# MCB-iMX7-WARP-v1_0_0.net
KiCad netlist of a schematic drawn in EAGLE
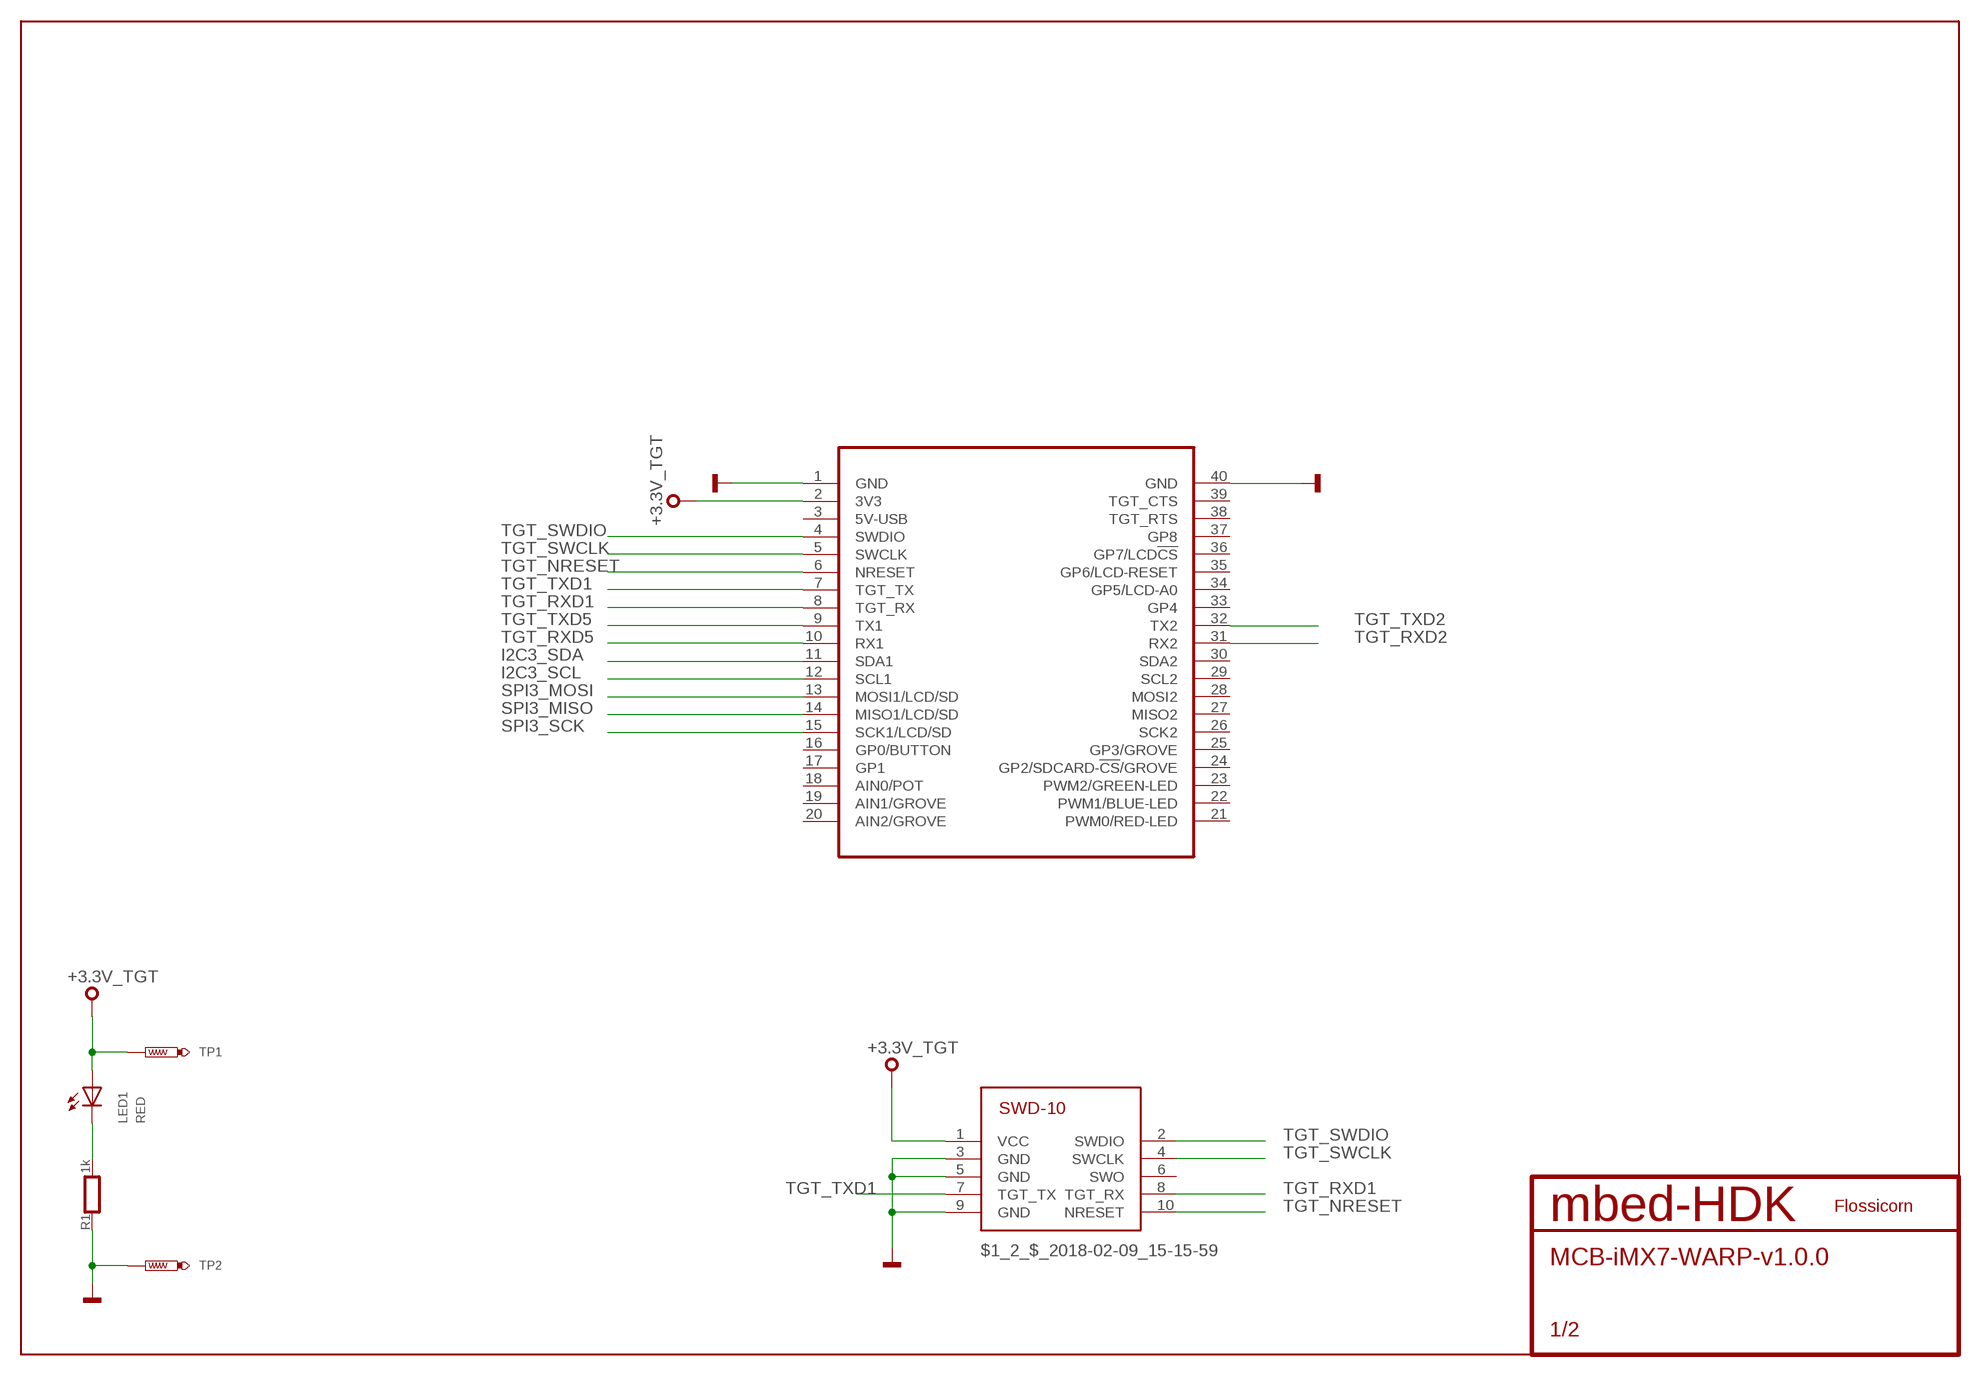
[diagram p0: schematic, sheet 1]
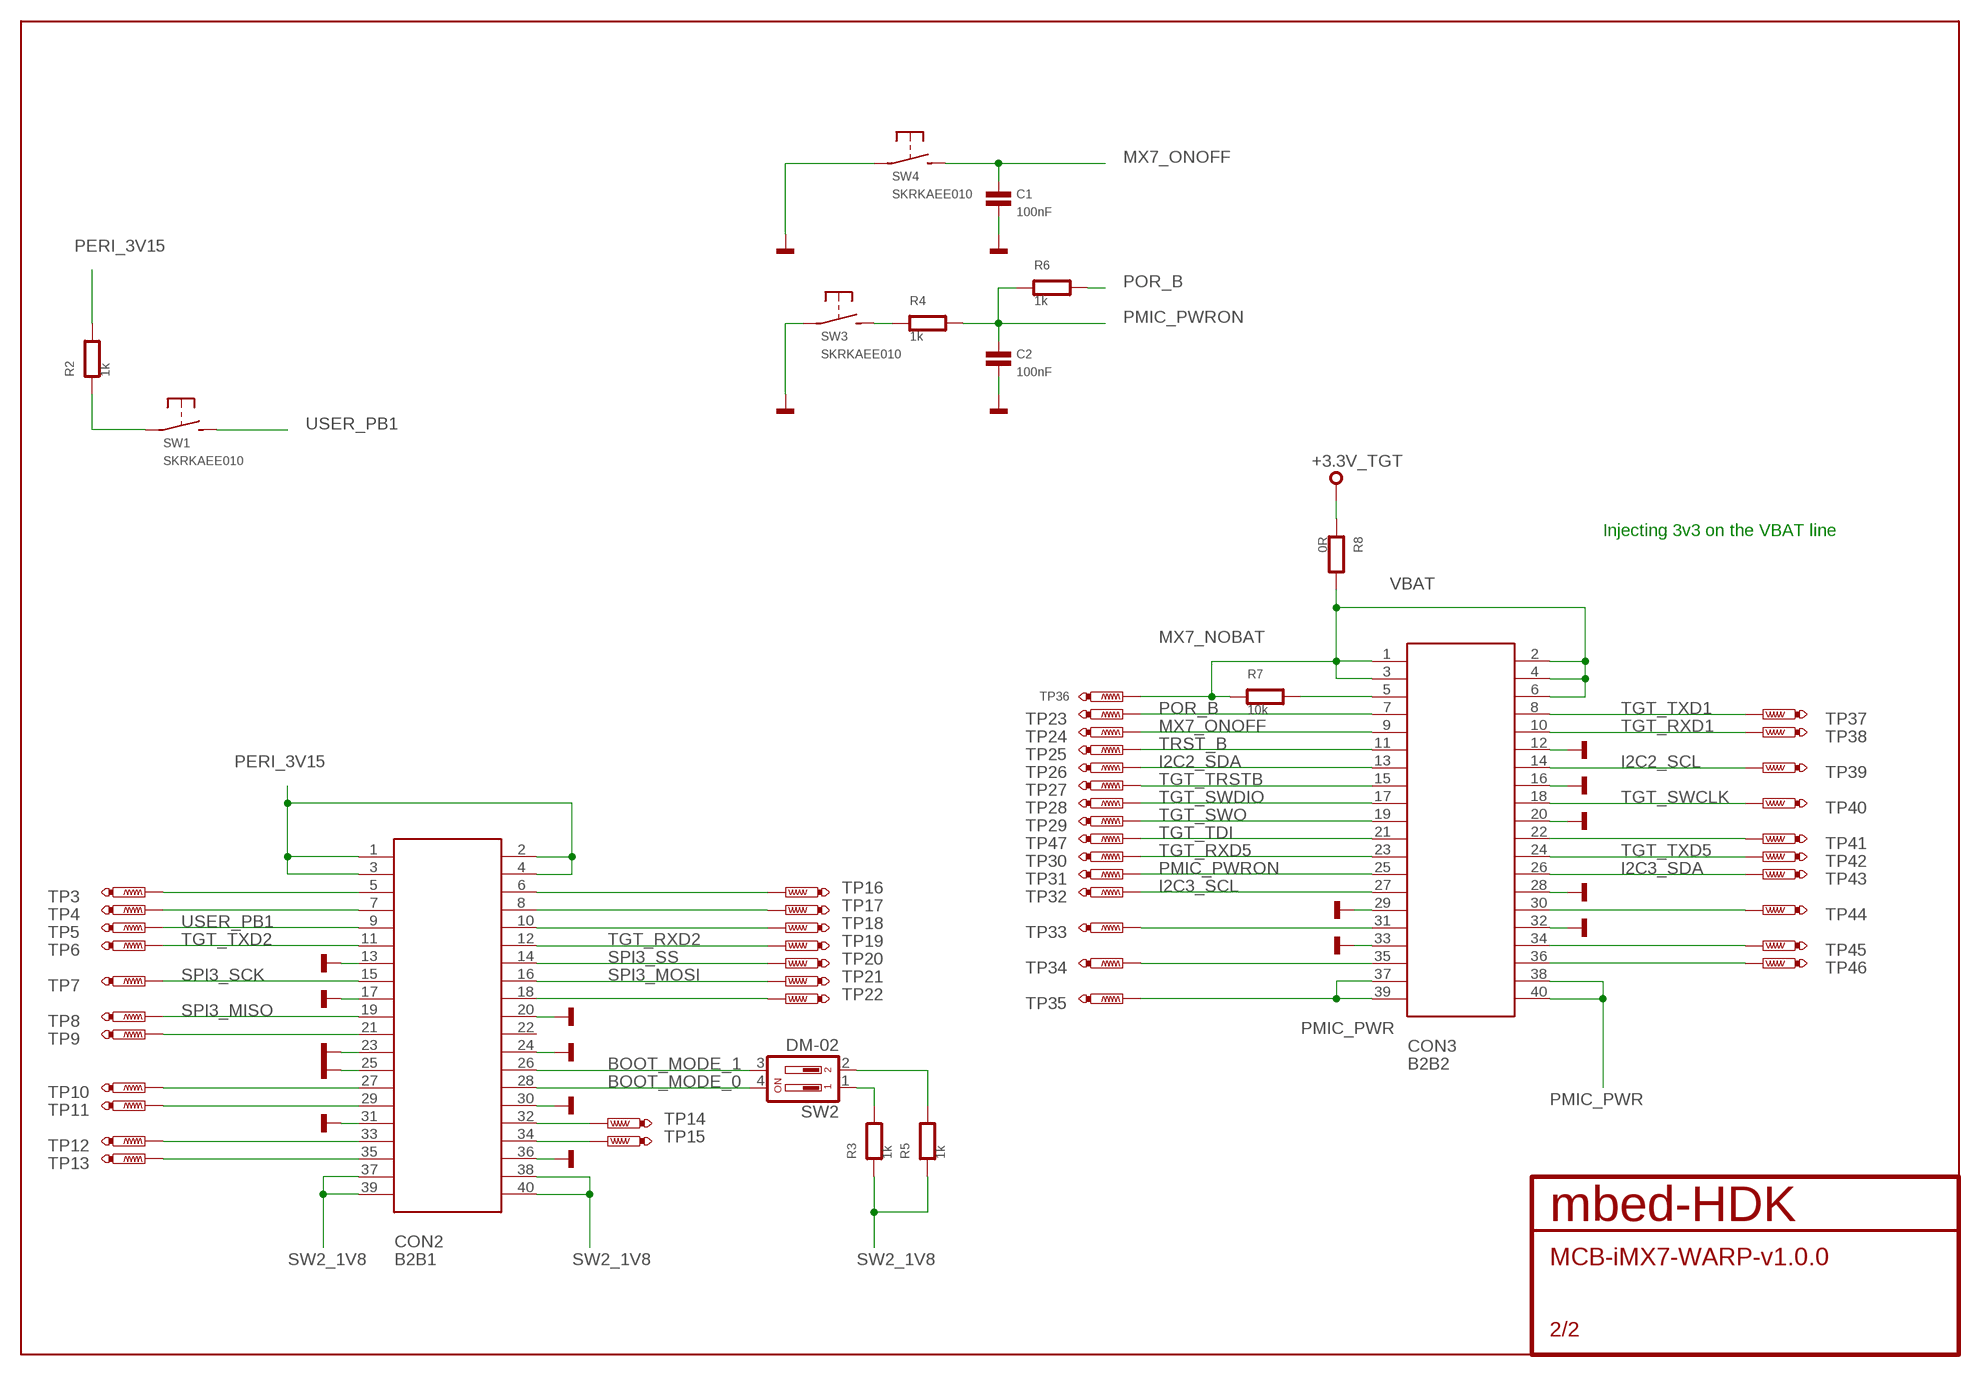
[diagram p1: schematic, sheet 2]

(export (version "E")
  (design (tool "Eeschema 10.0.6"))
  (components
    (comp (ref "C1")
      (value "100nF")
      (footprint "eagle-import:0603")
      (libsource (lib "eagle-import") (part "CAPACITOR0603"))
    )
    (comp (ref "C2")
      (value "100nF")
      (footprint "eagle-import:0603")
      (libsource (lib "eagle-import") (part "CAPACITOR0603"))
    )
    (comp (ref "CON2")
      (value "B2B1")
      (footprint "eagle-import:DF40HC-XX-40DS-XX-V")
      (libsource (lib "eagle-import") (part "DF40HC-XX-40DS-XX-V"))
    )
    (comp (ref "CON3")
      (value "B2B2")
      (footprint "eagle-import:DF40HC-XX-40DS-XX-V")
      (libsource (lib "eagle-import") (part "DF40HC-XX-40DS-XX-V"))
    )
    (comp (ref "R2")
      (value "1k")
      (footprint "eagle-import:0603")
      (libsource (lib "eagle-import") (part "RESISTOR0603"))
    )
    (comp (ref "R3")
      (value "1k")
      (footprint "eagle-import:0603")
      (libsource (lib "eagle-import") (part "RESISTOR0603"))
    )
    (comp (ref "R4")
      (value "1k")
      (footprint "eagle-import:0603")
      (libsource (lib "eagle-import") (part "RESISTOR0603"))
    )
    (comp (ref "R5")
      (value "1k")
      (footprint "eagle-import:0603")
      (libsource (lib "eagle-import") (part "RESISTOR0603"))
    )
    (comp (ref "R6")
      (value "1k")
      (footprint "eagle-import:0603")
      (libsource (lib "eagle-import") (part "RESISTOR0603"))
    )
    (comp (ref "R7")
      (value "10k")
      (footprint "eagle-import:0603")
      (libsource (lib "eagle-import") (part "RESISTOR0603"))
    )
    (comp (ref "R8")
      (value "0R")
      (footprint "eagle-import:0603")
      (libsource (lib "eagle-import") (part "RESISTOR0603"))
    )
    (comp (ref "SW1")
      (value "SKRKAEE010")
      (footprint "eagle-import:SKRKAEE010")
      (fields (field (name "MF") "ALPS"))
      (libsource (lib "eagle-import") (part "SKRKAEE010"))
    )
    (comp (ref "SW2")
      (value "DM-02")
      (footprint "eagle-import:DM-02")
      (libsource (lib "eagle-import") (part "DM-02"))
    )
    (comp (ref "SW3")
      (value "SKRKAEE010")
      (footprint "eagle-import:SKRKAEE010")
      (fields (field (name "MF") "ALPS"))
      (libsource (lib "eagle-import") (part "SKRKAEE010"))
    )
    (comp (ref "SW4")
      (value "SKRKAEE010")
      (footprint "eagle-import:SKRKAEE010")
      (fields (field (name "MF") "ALPS"))
      (libsource (lib "eagle-import") (part "SKRKAEE010"))
    )
    (comp (ref "TP3")
      (value "PTR1TP06R")
      (footprint "eagle-import:TP06R")
      (libsource (lib "eagle-import") (part "PTR1TP06R"))
    )
    (comp (ref "TP4")
      (value "PTR1TP06R")
      (footprint "eagle-import:TP06R")
      (libsource (lib "eagle-import") (part "PTR1TP06R"))
    )
    (comp (ref "TP5")
      (value "PTR1TP06R")
      (footprint "eagle-import:TP06R")
      (libsource (lib "eagle-import") (part "PTR1TP06R"))
    )
    (comp (ref "TP6")
      (value "PTR1TP06R")
      (footprint "eagle-import:TP06R")
      (libsource (lib "eagle-import") (part "PTR1TP06R"))
    )
    (comp (ref "TP7")
      (value "PTR1TP06R")
      (footprint "eagle-import:TP06R")
      (libsource (lib "eagle-import") (part "PTR1TP06R"))
    )
    (comp (ref "TP8")
      (value "PTR1TP06R")
      (footprint "eagle-import:TP06R")
      (libsource (lib "eagle-import") (part "PTR1TP06R"))
    )
    (comp (ref "TP9")
      (value "PTR1TP06R")
      (footprint "eagle-import:TP06R")
      (libsource (lib "eagle-import") (part "PTR1TP06R"))
    )
    (comp (ref "TP10")
      (value "PTR1TP06R")
      (footprint "eagle-import:TP06R")
      (libsource (lib "eagle-import") (part "PTR1TP06R"))
    )
    (comp (ref "TP11")
      (value "PTR1TP06R")
      (footprint "eagle-import:TP06R")
      (libsource (lib "eagle-import") (part "PTR1TP06R"))
    )
    (comp (ref "TP12")
      (value "PTR1TP06R")
      (footprint "eagle-import:TP06R")
      (libsource (lib "eagle-import") (part "PTR1TP06R"))
    )
    (comp (ref "TP13")
      (value "PTR1TP06R")
      (footprint "eagle-import:TP06R")
      (libsource (lib "eagle-import") (part "PTR1TP06R"))
    )
    (comp (ref "TP14")
      (value "PTR1TP06R")
      (footprint "eagle-import:TP06R")
      (libsource (lib "eagle-import") (part "PTR1TP06R"))
    )
    (comp (ref "TP15")
      (value "PTR1TP06R")
      (footprint "eagle-import:TP06R")
      (libsource (lib "eagle-import") (part "PTR1TP06R"))
    )
    (comp (ref "TP16")
      (value "PTR1TP06R")
      (footprint "eagle-import:TP06R")
      (libsource (lib "eagle-import") (part "PTR1TP06R"))
    )
    (comp (ref "TP17")
      (value "PTR1TP06R")
      (footprint "eagle-import:TP06R")
      (libsource (lib "eagle-import") (part "PTR1TP06R"))
    )
    (comp (ref "TP18")
      (value "PTR1TP06R")
      (footprint "eagle-import:TP06R")
      (libsource (lib "eagle-import") (part "PTR1TP06R"))
    )
    (comp (ref "TP19")
      (value "PTR1TP06R")
      (footprint "eagle-import:TP06R")
      (libsource (lib "eagle-import") (part "PTR1TP06R"))
    )
    (comp (ref "TP20")
      (value "PTR1TP06R")
      (footprint "eagle-import:TP06R")
      (libsource (lib "eagle-import") (part "PTR1TP06R"))
    )
    (comp (ref "TP21")
      (value "PTR1TP06R")
      (footprint "eagle-import:TP06R")
      (libsource (lib "eagle-import") (part "PTR1TP06R"))
    )
    (comp (ref "TP22")
      (value "PTR1TP06R")
      (footprint "eagle-import:TP06R")
      (libsource (lib "eagle-import") (part "PTR1TP06R"))
    )
    (comp (ref "TP23")
      (value "PTR1TP06R")
      (footprint "eagle-import:TP06R")
      (libsource (lib "eagle-import") (part "PTR1TP06R"))
    )
    (comp (ref "TP24")
      (value "PTR1TP06R")
      (footprint "eagle-import:TP06R")
      (libsource (lib "eagle-import") (part "PTR1TP06R"))
    )
    (comp (ref "TP25")
      (value "PTR1TP06R")
      (footprint "eagle-import:TP06R")
      (libsource (lib "eagle-import") (part "PTR1TP06R"))
    )
    (comp (ref "TP26")
      (value "PTR1TP06R")
      (footprint "eagle-import:TP06R")
      (libsource (lib "eagle-import") (part "PTR1TP06R"))
    )
    (comp (ref "TP27")
      (value "PTR1TP06R")
      (footprint "eagle-import:TP06R")
      (libsource (lib "eagle-import") (part "PTR1TP06R"))
    )
    (comp (ref "TP28")
      (value "PTR1TP06R")
      (footprint "eagle-import:TP06R")
      (libsource (lib "eagle-import") (part "PTR1TP06R"))
    )
    (comp (ref "TP29")
      (value "PTR1TP06R")
      (footprint "eagle-import:TP06R")
      (libsource (lib "eagle-import") (part "PTR1TP06R"))
    )
    (comp (ref "TP30")
      (value "PTR1TP06R")
      (footprint "eagle-import:TP06R")
      (libsource (lib "eagle-import") (part "PTR1TP06R"))
    )
    (comp (ref "TP31")
      (value "PTR1TP06R")
      (footprint "eagle-import:TP06R")
      (libsource (lib "eagle-import") (part "PTR1TP06R"))
    )
    (comp (ref "TP32")
      (value "PTR1TP06R")
      (footprint "eagle-import:TP06R")
      (libsource (lib "eagle-import") (part "PTR1TP06R"))
    )
    (comp (ref "TP33")
      (value "PTR1TP06R")
      (footprint "eagle-import:TP06R")
      (libsource (lib "eagle-import") (part "PTR1TP06R"))
    )
    (comp (ref "TP34")
      (value "PTR1TP06R")
      (footprint "eagle-import:TP06R")
      (libsource (lib "eagle-import") (part "PTR1TP06R"))
    )
    (comp (ref "TP35")
      (value "PTR1TP10R")
      (footprint "eagle-import:TP10R")
      (libsource (lib "eagle-import") (part "PTR1TP10R"))
    )
    (comp (ref "TP36")
      (value "TEST-POINT-50R-SMD")
      (footprint "eagle-import:TP50-SMD")
      (libsource (lib "eagle-import") (part "TEST-POINT-50R-SMD"))
    )
    (comp (ref "TP37")
      (value "PTR1TP06R")
      (footprint "eagle-import:TP06R")
      (libsource (lib "eagle-import") (part "PTR1TP06R"))
    )
    (comp (ref "TP38")
      (value "PTR1TP06R")
      (footprint "eagle-import:TP06R")
      (libsource (lib "eagle-import") (part "PTR1TP06R"))
    )
    (comp (ref "TP39")
      (value "PTR1TP06R")
      (footprint "eagle-import:TP06R")
      (libsource (lib "eagle-import") (part "PTR1TP06R"))
    )
    (comp (ref "TP40")
      (value "PTR1TP06R")
      (footprint "eagle-import:TP06R")
      (libsource (lib "eagle-import") (part "PTR1TP06R"))
    )
    (comp (ref "TP41")
      (value "PTR1TP06R")
      (footprint "eagle-import:TP06R")
      (libsource (lib "eagle-import") (part "PTR1TP06R"))
    )
    (comp (ref "TP42")
      (value "PTR1TP06R")
      (footprint "eagle-import:TP06R")
      (libsource (lib "eagle-import") (part "PTR1TP06R"))
    )
    (comp (ref "TP43")
      (value "PTR1TP06R")
      (footprint "eagle-import:TP06R")
      (libsource (lib "eagle-import") (part "PTR1TP06R"))
    )
    (comp (ref "TP44")
      (value "PTR1TP06R")
      (footprint "eagle-import:TP06R")
      (libsource (lib "eagle-import") (part "PTR1TP06R"))
    )
    (comp (ref "TP45")
      (value "PTR1TP06R")
      (footprint "eagle-import:TP06R")
      (libsource (lib "eagle-import") (part "PTR1TP06R"))
    )
    (comp (ref "TP46")
      (value "PTR1TP06R")
      (footprint "eagle-import:TP06R")
      (libsource (lib "eagle-import") (part "PTR1TP06R"))
    )
    (comp (ref "TP47")
      (value "PTR1TP06R")
      (footprint "eagle-import:TP06R")
      (libsource (lib "eagle-import") (part "PTR1TP06R"))
    )
    (comp (ref "$1_2_$_2018-02-09_15-15-59")
      (value "SWD-10/TC2050_SMD")
      (footprint "eagle-import:FTSH-105-02")
      (libsource (lib "eagle-import") (part "SWD-10/TC2050_SMD"))
    )
    (comp (ref "LED1")
      (value "RED")
      (footprint "eagle-import:CHIPLED_0603")
      (fields (field (name "MF") "Wurth Electronics Inc"))
      (libsource (lib "eagle-import") (part "SMD_LED0603"))
    )
    (comp (ref "MOD1")
      (value "MODULE_DAUGHTER")
      (footprint "eagle-import:MODULE_DAUGHTER")
      (libsource (lib "eagle-import") (part "MODULE_DAUGHTER"))
    )
    (comp (ref "R1")
      (value "1k")
      (footprint "eagle-import:0603")
      (libsource (lib "eagle-import") (part "RESISTOR0603"))
    )
    (comp (ref "SS1")
      (value "FLOSSICORN0.5")
      (footprint "eagle-import:FLOSSICORN-0.5")
      (libsource (lib "eagle-import") (part "FLOSSICORN0.5"))
    )
    (comp (ref "TP1")
      (value "TEST-POINT-50R-PTH")
      (footprint "eagle-import:TP50-PTH")
      (libsource (lib "eagle-import") (part "TEST-POINT-50R-PTH"))
    )
    (comp (ref "TP2")
      (value "TEST-POINT-50R-PTH")
      (footprint "eagle-import:TP50-PTH")
      (libsource (lib "eagle-import") (part "TEST-POINT-50R-PTH"))
    )
  )
  (nets
    (net (code "1") (name "+3.3V_TGT") (class "Default")
      (node (ref "$1_2_$_2018-02-09_15-15-59") (pin "1") (pinfunction "VCC_1") (pintype "bidirectional"))
      (node (ref "LED1") (pin "A") (pinfunction "A_A") (pintype "passive"))
      (node (ref "MOD1") (pin "2") (pinfunction "3V3_2") (pintype "bidirectional"))
      (node (ref "R8") (pin "1") (pinfunction "P$1_1") (pintype "passive"))
      (node (ref "TP1") (pin "TP") (pinfunction "TP_TP") (pintype "input"))
    )
    (net (code "2") (name "BOOT_MODE_0") (class "Default")
      (node (ref "CON2") (pin "28") (pinfunction "P$28_28") (pintype "bidirectional"))
      (node (ref "SW2") (pin "4") (pinfunction "4_4") (pintype "passive"))
    )
    (net (code "3") (name "BOOT_MODE_1") (class "Default")
      (node (ref "CON2") (pin "26") (pinfunction "P$26_26") (pintype "bidirectional"))
      (node (ref "SW2") (pin "3") (pinfunction "3_3") (pintype "passive"))
    )
    (net (code "4") (name "GND") (class "Default")
      (node (ref "$1_2_$_2018-02-09_15-15-59") (pin "3") (pinfunction "GND_3") (pintype "bidirectional"))
      (node (ref "$1_2_$_2018-02-09_15-15-59") (pin "5") (pinfunction "GND_5") (pintype "bidirectional"))
      (node (ref "$1_2_$_2018-02-09_15-15-59") (pin "9") (pinfunction "GND_9") (pintype "bidirectional"))
      (node (ref "C1") (pin "2") (pinfunction "P$2_2") (pintype "passive"))
      (node (ref "C2") (pin "2") (pinfunction "P$2_2") (pintype "passive"))
      (node (ref "CON2") (pin "13") (pinfunction "P$13_13") (pintype "bidirectional"))
      (node (ref "CON2") (pin "17") (pinfunction "P$17_17") (pintype "bidirectional"))
      (node (ref "CON2") (pin "20") (pinfunction "P$20_20") (pintype "bidirectional"))
      (node (ref "CON2") (pin "23") (pinfunction "P$23_23") (pintype "bidirectional"))
      (node (ref "CON2") (pin "24") (pinfunction "P$24_24") (pintype "bidirectional"))
      (node (ref "CON2") (pin "25") (pinfunction "P$25_25") (pintype "bidirectional"))
      (node (ref "CON2") (pin "30") (pinfunction "P$30_30") (pintype "bidirectional"))
      (node (ref "CON2") (pin "31") (pinfunction "P$31_31") (pintype "bidirectional"))
      (node (ref "CON2") (pin "36") (pinfunction "P$36_36") (pintype "bidirectional"))
      (node (ref "CON3") (pin "12") (pinfunction "P$12_12") (pintype "bidirectional"))
      (node (ref "CON3") (pin "16") (pinfunction "P$16_16") (pintype "bidirectional"))
      (node (ref "CON3") (pin "20") (pinfunction "P$20_20") (pintype "bidirectional"))
      (node (ref "CON3") (pin "28") (pinfunction "P$28_28") (pintype "bidirectional"))
      (node (ref "CON3") (pin "29") (pinfunction "P$29_29") (pintype "bidirectional"))
      (node (ref "CON3") (pin "32") (pinfunction "P$32_32") (pintype "bidirectional"))
      (node (ref "CON3") (pin "33") (pinfunction "P$33_33") (pintype "bidirectional"))
      (node (ref "MOD1") (pin "1") (pinfunction "GND_1") (pintype "bidirectional"))
      (node (ref "MOD1") (pin "40") (pinfunction "GND_40") (pintype "bidirectional"))
      (node (ref "R1") (pin "1") (pinfunction "P$1_1") (pintype "passive"))
      (node (ref "SW3") (pin "P$1") (pinfunction "P_P$1") (pintype "passive"))
      (node (ref "SW4") (pin "P$1") (pinfunction "P_P$1") (pintype "passive"))
      (node (ref "TP2") (pin "TP") (pinfunction "TP_TP") (pintype "input"))
    )
    (net (code "5") (name "I2C2_SCL") (class "Default")
      (node (ref "CON3") (pin "14") (pinfunction "P$14_14") (pintype "bidirectional"))
      (node (ref "TP39") (pin "TP") (pinfunction "TP_TP") (pintype "input"))
    )
    (net (code "6") (name "I2C2_SDA") (class "Default")
      (node (ref "CON3") (pin "13") (pinfunction "P$13_13") (pintype "bidirectional"))
      (node (ref "TP26") (pin "TP") (pinfunction "TP_TP") (pintype "input"))
    )
    (net (code "7") (name "I2C3_SCL") (class "Default")
      (node (ref "CON3") (pin "27") (pinfunction "P$27_27") (pintype "bidirectional"))
      (node (ref "MOD1") (pin "12") (pinfunction "SCL1_12") (pintype "bidirectional"))
      (node (ref "TP32") (pin "TP") (pinfunction "TP_TP") (pintype "input"))
    )
    (net (code "8") (name "I2C3_SDA") (class "Default")
      (node (ref "CON3") (pin "26") (pinfunction "P$26_26") (pintype "bidirectional"))
      (node (ref "MOD1") (pin "11") (pinfunction "SDA1_11") (pintype "bidirectional"))
      (node (ref "TP43") (pin "TP") (pinfunction "TP_TP") (pintype "input"))
    )
    (net (code "9") (name "MX7_NOBAT") (class "Default")
      (node (ref "CON3") (pin "5") (pinfunction "P$5_5") (pintype "bidirectional"))
      (node (ref "R7") (pin "2") (pinfunction "P$2_2") (pintype "passive"))
    )
    (net (code "10") (name "MX7_ONOFF") (class "Default")
      (node (ref "C1") (pin "1") (pinfunction "P$1_1") (pintype "passive"))
      (node (ref "CON3") (pin "9") (pinfunction "P$9_9") (pintype "bidirectional"))
      (node (ref "SW4") (pin "P$2") (pinfunction "S_P$2") (pintype "passive"))
      (node (ref "TP24") (pin "TP") (pinfunction "TP_TP") (pintype "input"))
    )
    (net (code "11") (name "Net-(CON2-P$5)") (class "Default")
      (node (ref "CON2") (pin "5") (pinfunction "P$5_5") (pintype "bidirectional"))
      (node (ref "TP3") (pin "TP") (pinfunction "TP_TP") (pintype "input"))
    )
    (net (code "12") (name "Net-(CON2-P$6)") (class "Default")
      (node (ref "CON2") (pin "6") (pinfunction "P$6_6") (pintype "bidirectional"))
      (node (ref "TP16") (pin "TP") (pinfunction "TP_TP") (pintype "input"))
    )
    (net (code "13") (name "Net-(CON2-P$7)") (class "Default")
      (node (ref "CON2") (pin "7") (pinfunction "P$7_7") (pintype "bidirectional"))
      (node (ref "TP4") (pin "TP") (pinfunction "TP_TP") (pintype "input"))
    )
    (net (code "14") (name "Net-(CON2-P$8)") (class "Default")
      (node (ref "CON2") (pin "8") (pinfunction "P$8_8") (pintype "bidirectional"))
      (node (ref "TP17") (pin "TP") (pinfunction "TP_TP") (pintype "input"))
    )
    (net (code "15") (name "Net-(CON2-P$10)") (class "Default")
      (node (ref "CON2") (pin "10") (pinfunction "P$10_10") (pintype "bidirectional"))
      (node (ref "TP18") (pin "TP") (pinfunction "TP_TP") (pintype "input"))
    )
    (net (code "16") (name "Net-(CON2-P$18)") (class "Default")
      (node (ref "CON2") (pin "18") (pinfunction "P$18_18") (pintype "bidirectional"))
      (node (ref "TP22") (pin "TP") (pinfunction "TP_TP") (pintype "input"))
    )
    (net (code "17") (name "Net-(CON2-P$21)") (class "Default")
      (node (ref "CON2") (pin "21") (pinfunction "P$21_21") (pintype "bidirectional"))
      (node (ref "TP9") (pin "TP") (pinfunction "TP_TP") (pintype "input"))
    )
    (net (code "18") (name "Net-(CON2-P$27)") (class "Default")
      (node (ref "CON2") (pin "27") (pinfunction "P$27_27") (pintype "bidirectional"))
      (node (ref "TP10") (pin "TP") (pinfunction "TP_TP") (pintype "input"))
    )
    (net (code "19") (name "Net-(CON2-P$29)") (class "Default")
      (node (ref "CON2") (pin "29") (pinfunction "P$29_29") (pintype "bidirectional"))
      (node (ref "TP11") (pin "TP") (pinfunction "TP_TP") (pintype "input"))
    )
    (net (code "20") (name "Net-(CON2-P$32)") (class "Default")
      (node (ref "CON2") (pin "32") (pinfunction "P$32_32") (pintype "bidirectional"))
      (node (ref "TP14") (pin "TP") (pinfunction "TP_TP") (pintype "input"))
    )
    (net (code "21") (name "Net-(CON2-P$33)") (class "Default")
      (node (ref "CON2") (pin "33") (pinfunction "P$33_33") (pintype "bidirectional"))
      (node (ref "TP12") (pin "TP") (pinfunction "TP_TP") (pintype "input"))
    )
    (net (code "22") (name "Net-(CON2-P$34)") (class "Default")
      (node (ref "CON2") (pin "34") (pinfunction "P$34_34") (pintype "bidirectional"))
      (node (ref "TP15") (pin "TP") (pinfunction "TP_TP") (pintype "input"))
    )
    (net (code "23") (name "Net-(CON2-P$35)") (class "Default")
      (node (ref "CON2") (pin "35") (pinfunction "P$35_35") (pintype "bidirectional"))
      (node (ref "TP13") (pin "TP") (pinfunction "TP_TP") (pintype "input"))
    )
    (net (code "24") (name "Net-(CON3-P$22)") (class "Default")
      (node (ref "CON3") (pin "22") (pinfunction "P$22_22") (pintype "bidirectional"))
      (node (ref "TP41") (pin "TP") (pinfunction "TP_TP") (pintype "input"))
    )
    (net (code "25") (name "Net-(CON3-P$30)") (class "Default")
      (node (ref "CON3") (pin "30") (pinfunction "P$30_30") (pintype "bidirectional"))
      (node (ref "TP44") (pin "TP") (pinfunction "TP_TP") (pintype "input"))
    )
    (net (code "26") (name "Net-(CON3-P$31)") (class "Default")
      (node (ref "CON3") (pin "31") (pinfunction "P$31_31") (pintype "bidirectional"))
      (node (ref "TP33") (pin "TP") (pinfunction "TP_TP") (pintype "input"))
    )
    (net (code "27") (name "Net-(CON3-P$34)") (class "Default")
      (node (ref "CON3") (pin "34") (pinfunction "P$34_34") (pintype "bidirectional"))
      (node (ref "TP45") (pin "TP") (pinfunction "TP_TP") (pintype "input"))
    )
    (net (code "28") (name "Net-(CON3-P$35)") (class "Default")
      (node (ref "CON3") (pin "35") (pinfunction "P$35_35") (pintype "bidirectional"))
      (node (ref "TP34") (pin "TP") (pinfunction "TP_TP") (pintype "input"))
    )
    (net (code "29") (name "Net-(CON3-P$36)") (class "Default")
      (node (ref "CON3") (pin "36") (pinfunction "P$36_36") (pintype "bidirectional"))
      (node (ref "TP46") (pin "TP") (pinfunction "TP_TP") (pintype "input"))
    )
    (net (code "30") (name "Net-(R1-P$2)") (class "Default")
      (node (ref "LED1") (pin "C") (pinfunction "C_C") (pintype "passive"))
      (node (ref "R1") (pin "2") (pinfunction "P$2_2") (pintype "passive"))
    )
    (net (code "31") (name "Net-(R2-P$1)") (class "Default")
      (node (ref "R2") (pin "1") (pinfunction "P$1_1") (pintype "passive"))
      (node (ref "SW1") (pin "P$1") (pinfunction "P_P$1") (pintype "passive"))
    )
    (net (code "32") (name "Net-(R3-P$2)") (class "Default")
      (node (ref "R3") (pin "2") (pinfunction "P$2_2") (pintype "passive"))
      (node (ref "SW2") (pin "1") (pinfunction "1_1") (pintype "passive"))
    )
    (net (code "33") (name "Net-(R4-P$1)") (class "Default")
      (node (ref "R4") (pin "1") (pinfunction "P$1_1") (pintype "passive"))
      (node (ref "SW3") (pin "P$2") (pinfunction "S_P$2") (pintype "passive"))
    )
    (net (code "34") (name "Net-(R5-P$2)") (class "Default")
      (node (ref "R5") (pin "2") (pinfunction "P$2_2") (pintype "passive"))
      (node (ref "SW2") (pin "2") (pinfunction "2_2") (pintype "passive"))
    )
    (net (code "35") (name "PERI_3V15") (class "Default")
      (node (ref "CON2") (pin "1") (pinfunction "P$1_1") (pintype "bidirectional"))
      (node (ref "CON2") (pin "2") (pinfunction "P$2_2") (pintype "bidirectional"))
      (node (ref "CON2") (pin "3") (pinfunction "P$3_3") (pintype "bidirectional"))
      (node (ref "CON2") (pin "4") (pinfunction "P$4_4") (pintype "bidirectional"))
      (node (ref "R2") (pin "2") (pinfunction "P$2_2") (pintype "passive"))
    )
    (net (code "36") (name "PMIC_PWR") (class "Default")
      (node (ref "CON3") (pin "37") (pinfunction "P$37_37") (pintype "bidirectional"))
      (node (ref "CON3") (pin "38") (pinfunction "P$38_38") (pintype "bidirectional"))
      (node (ref "CON3") (pin "39") (pinfunction "P$39_39") (pintype "bidirectional"))
      (node (ref "CON3") (pin "40") (pinfunction "P$40_40") (pintype "bidirectional"))
      (node (ref "TP35") (pin "TP") (pinfunction "TP_TP") (pintype "input"))
    )
    (net (code "37") (name "PMIC_PWRON") (class "Default")
      (node (ref "C2") (pin "1") (pinfunction "P$1_1") (pintype "passive"))
      (node (ref "CON3") (pin "25") (pinfunction "P$25_25") (pintype "bidirectional"))
      (node (ref "R4") (pin "2") (pinfunction "P$2_2") (pintype "passive"))
      (node (ref "R6") (pin "1") (pinfunction "P$1_1") (pintype "passive"))
      (node (ref "TP31") (pin "TP") (pinfunction "TP_TP") (pintype "input"))
    )
    (net (code "38") (name "POR_B") (class "Default")
      (node (ref "CON3") (pin "7") (pinfunction "P$7_7") (pintype "bidirectional"))
      (node (ref "R6") (pin "2") (pinfunction "P$2_2") (pintype "passive"))
      (node (ref "TP23") (pin "TP") (pinfunction "TP_TP") (pintype "input"))
    )
    (net (code "39") (name "SPI3_MISO") (class "Default")
      (node (ref "CON2") (pin "19") (pinfunction "P$19_19") (pintype "bidirectional"))
      (node (ref "MOD1") (pin "14") (pinfunction "MISO1/LCD/SD_14") (pintype "bidirectional"))
      (node (ref "TP8") (pin "TP") (pinfunction "TP_TP") (pintype "input"))
    )
    (net (code "40") (name "SPI3_MOSI") (class "Default")
      (node (ref "CON2") (pin "16") (pinfunction "P$16_16") (pintype "bidirectional"))
      (node (ref "MOD1") (pin "13") (pinfunction "MOSI1/LCD/SD_13") (pintype "bidirectional"))
      (node (ref "TP21") (pin "TP") (pinfunction "TP_TP") (pintype "input"))
    )
    (net (code "41") (name "SPI3_SCK") (class "Default")
      (node (ref "CON2") (pin "15") (pinfunction "P$15_15") (pintype "bidirectional"))
      (node (ref "MOD1") (pin "15") (pinfunction "SCK1/LCD/SD_15") (pintype "bidirectional"))
      (node (ref "TP7") (pin "TP") (pinfunction "TP_TP") (pintype "input"))
    )
    (net (code "42") (name "SPI3_SS") (class "Default")
      (node (ref "CON2") (pin "14") (pinfunction "P$14_14") (pintype "bidirectional"))
      (node (ref "TP20") (pin "TP") (pinfunction "TP_TP") (pintype "input"))
    )
    (net (code "43") (name "SW2_1V8") (class "Default")
      (node (ref "CON2") (pin "37") (pinfunction "P$37_37") (pintype "bidirectional"))
      (node (ref "CON2") (pin "38") (pinfunction "P$38_38") (pintype "bidirectional"))
      (node (ref "CON2") (pin "39") (pinfunction "P$39_39") (pintype "bidirectional"))
      (node (ref "CON2") (pin "40") (pinfunction "P$40_40") (pintype "bidirectional"))
      (node (ref "R3") (pin "1") (pinfunction "P$1_1") (pintype "passive"))
      (node (ref "R5") (pin "1") (pinfunction "P$1_1") (pintype "passive"))
    )
    (net (code "44") (name "TGT_NRESET") (class "Default")
      (node (ref "$1_2_$_2018-02-09_15-15-59") (pin "10") (pinfunction "NRESET_10") (pintype "bidirectional"))
      (node (ref "MOD1") (pin "6") (pinfunction "NRESET_6") (pintype "bidirectional"))
    )
    (net (code "45") (name "TGT_RXD1") (class "Default")
      (node (ref "$1_2_$_2018-02-09_15-15-59") (pin "8") (pinfunction "TGT_RX_8") (pintype "bidirectional"))
      (node (ref "CON3") (pin "10") (pinfunction "P$10_10") (pintype "bidirectional"))
      (node (ref "MOD1") (pin "8") (pinfunction "TGT_RX_8") (pintype "bidirectional"))
      (node (ref "TP38") (pin "TP") (pinfunction "TP_TP") (pintype "input"))
    )
    (net (code "46") (name "TGT_RXD2") (class "Default")
      (node (ref "CON2") (pin "12") (pinfunction "P$12_12") (pintype "bidirectional"))
      (node (ref "MOD1") (pin "31") (pinfunction "RX2_31") (pintype "bidirectional"))
      (node (ref "TP19") (pin "TP") (pinfunction "TP_TP") (pintype "input"))
    )
    (net (code "47") (name "TGT_RXD5") (class "Default")
      (node (ref "CON3") (pin "23") (pinfunction "P$23_23") (pintype "bidirectional"))
      (node (ref "MOD1") (pin "10") (pinfunction "RX1_10") (pintype "bidirectional"))
      (node (ref "TP30") (pin "TP") (pinfunction "TP_TP") (pintype "input"))
    )
    (net (code "48") (name "TGT_SWCLK") (class "Default")
      (node (ref "$1_2_$_2018-02-09_15-15-59") (pin "4") (pinfunction "SWCLK_4") (pintype "bidirectional"))
      (node (ref "CON3") (pin "18") (pinfunction "P$18_18") (pintype "bidirectional"))
      (node (ref "MOD1") (pin "5") (pinfunction "SWCLK_5") (pintype "bidirectional"))
      (node (ref "TP40") (pin "TP") (pinfunction "TP_TP") (pintype "input"))
    )
    (net (code "49") (name "TGT_SWDIO") (class "Default")
      (node (ref "$1_2_$_2018-02-09_15-15-59") (pin "2") (pinfunction "SWDIO_2") (pintype "bidirectional"))
      (node (ref "CON3") (pin "17") (pinfunction "P$17_17") (pintype "bidirectional"))
      (node (ref "MOD1") (pin "4") (pinfunction "SWDIO_4") (pintype "bidirectional"))
      (node (ref "TP28") (pin "TP") (pinfunction "TP_TP") (pintype "input"))
    )
    (net (code "50") (name "TGT_SWO") (class "Default")
      (node (ref "CON3") (pin "19") (pinfunction "P$19_19") (pintype "bidirectional"))
      (node (ref "TP29") (pin "TP") (pinfunction "TP_TP") (pintype "input"))
    )
    (net (code "51") (name "TGT_TDI") (class "Default")
      (node (ref "CON3") (pin "21") (pinfunction "P$21_21") (pintype "bidirectional"))
      (node (ref "TP47") (pin "TP") (pinfunction "TP_TP") (pintype "input"))
    )
    (net (code "52") (name "TGT_TRSTB") (class "Default")
      (node (ref "CON3") (pin "15") (pinfunction "P$15_15") (pintype "bidirectional"))
      (node (ref "TP27") (pin "TP") (pinfunction "TP_TP") (pintype "input"))
    )
    (net (code "53") (name "TGT_TXD1") (class "Default")
      (node (ref "$1_2_$_2018-02-09_15-15-59") (pin "7") (pinfunction "TGT_TX_7") (pintype "bidirectional"))
      (node (ref "CON3") (pin "8") (pinfunction "P$8_8") (pintype "bidirectional"))
      (node (ref "MOD1") (pin "7") (pinfunction "TGT_TX_7") (pintype "bidirectional"))
      (node (ref "TP37") (pin "TP") (pinfunction "TP_TP") (pintype "input"))
    )
    (net (code "54") (name "TGT_TXD2") (class "Default")
      (node (ref "CON2") (pin "11") (pinfunction "P$11_11") (pintype "bidirectional"))
      (node (ref "MOD1") (pin "32") (pinfunction "TX2_32") (pintype "bidirectional"))
      (node (ref "TP6") (pin "TP") (pinfunction "TP_TP") (pintype "input"))
    )
    (net (code "55") (name "TGT_TXD5") (class "Default")
      (node (ref "CON3") (pin "24") (pinfunction "P$24_24") (pintype "bidirectional"))
      (node (ref "MOD1") (pin "9") (pinfunction "TX1_9") (pintype "bidirectional"))
      (node (ref "TP42") (pin "TP") (pinfunction "TP_TP") (pintype "input"))
    )
    (net (code "56") (name "TRST_B") (class "Default")
      (node (ref "CON3") (pin "11") (pinfunction "P$11_11") (pintype "bidirectional"))
      (node (ref "TP25") (pin "TP") (pinfunction "TP_TP") (pintype "input"))
    )
    (net (code "57") (name "USER_PB1") (class "Default")
      (node (ref "CON2") (pin "9") (pinfunction "P$9_9") (pintype "bidirectional"))
      (node (ref "SW1") (pin "P$2") (pinfunction "S_P$2") (pintype "passive"))
      (node (ref "TP5") (pin "TP") (pinfunction "TP_TP") (pintype "input"))
    )
    (net (code "58") (name "VBAT") (class "Default")
      (node (ref "CON3") (pin "1") (pinfunction "P$1_1") (pintype "bidirectional"))
      (node (ref "CON3") (pin "2") (pinfunction "P$2_2") (pintype "bidirectional"))
      (node (ref "CON3") (pin "3") (pinfunction "P$3_3") (pintype "bidirectional"))
      (node (ref "CON3") (pin "4") (pinfunction "P$4_4") (pintype "bidirectional"))
      (node (ref "CON3") (pin "6") (pinfunction "P$6_6") (pintype "bidirectional"))
      (node (ref "R7") (pin "1") (pinfunction "P$1_1") (pintype "passive"))
      (node (ref "R8") (pin "2") (pinfunction "P$2_2") (pintype "passive"))
      (node (ref "TP36") (pin "TP") (pinfunction "TP_TP") (pintype "input"))
    )
    (net (code "59") (name "unconnected-($1_2_$_2018-02-09_15-15-59-SWO-Pad6)") (class "Default")
      (node (ref "$1_2_$_2018-02-09_15-15-59") (pin "6") (pinfunction "SWO_6") (pintype "bidirectional"))
    )
    (net (code "60") (name "unconnected-(CON2-P$22-Pad22)") (class "Default")
      (node (ref "CON2") (pin "22") (pinfunction "P$22_22") (pintype "bidirectional"))
    )
    (net (code "61") (name "unconnected-(MOD1-5V-USB-Pad3)") (class "Default")
      (node (ref "MOD1") (pin "3") (pinfunction "5V-USB_3") (pintype "bidirectional"))
    )
    (net (code "62") (name "unconnected-(MOD1-AIN0{slash}POT-Pad18)") (class "Default")
      (node (ref "MOD1") (pin "18") (pinfunction "AIN0/POT_18") (pintype "bidirectional"))
    )
    (net (code "63") (name "unconnected-(MOD1-AIN1{slash}GROVE-Pad19)") (class "Default")
      (node (ref "MOD1") (pin "19") (pinfunction "AIN1/GROVE_19") (pintype "bidirectional"))
    )
    (net (code "64") (name "unconnected-(MOD1-AIN2{slash}GROVE-Pad20)") (class "Default")
      (node (ref "MOD1") (pin "20") (pinfunction "AIN2/GROVE_20") (pintype "bidirectional"))
    )
    (net (code "65") (name "unconnected-(MOD1-GP0{slash}BUTTON-Pad16)") (class "Default")
      (node (ref "MOD1") (pin "16") (pinfunction "GP0/BUTTON_16") (pintype "bidirectional"))
    )
    (net (code "66") (name "unconnected-(MOD1-GP1-Pad17)") (class "Default")
      (node (ref "MOD1") (pin "17") (pinfunction "GP1_17") (pintype "bidirectional"))
    )
    (net (code "67") (name "unconnected-(MOD1-GP2{slash}SDCARD-~{CS}{slash}GROVE-Pad24)") (class "Default")
      (node (ref "MOD1") (pin "24") (pinfunction "GP2/SDCARD-~{CS}/GROVE_24") (pintype "bidirectional"))
    )
    (net (code "68") (name "unconnected-(MOD1-GP3{slash}GROVE-Pad25)") (class "Default")
      (node (ref "MOD1") (pin "25") (pinfunction "GP3/GROVE_25") (pintype "bidirectional"))
    )
    (net (code "69") (name "unconnected-(MOD1-GP4-Pad33)") (class "Default")
      (node (ref "MOD1") (pin "33") (pinfunction "GP4_33") (pintype "bidirectional"))
    )
    (net (code "70") (name "unconnected-(MOD1-GP5{slash}LCD-A0-Pad34)") (class "Default")
      (node (ref "MOD1") (pin "34") (pinfunction "GP5/LCD-A0_34") (pintype "bidirectional"))
    )
    (net (code "71") (name "unconnected-(MOD1-GP6{slash}LCD-RESET-Pad35)") (class "Default")
      (node (ref "MOD1") (pin "35") (pinfunction "GP6/LCD-RESET_35") (pintype "bidirectional"))
    )
    (net (code "72") (name "unconnected-(MOD1-GP7{slash}LCD~{CS}-Pad36)") (class "Default")
      (node (ref "MOD1") (pin "36") (pinfunction "GP7/LCD~{CS}_36") (pintype "bidirectional"))
    )
    (net (code "73") (name "unconnected-(MOD1-GP8-Pad37)") (class "Default")
      (node (ref "MOD1") (pin "37") (pinfunction "GP8_37") (pintype "bidirectional"))
    )
    (net (code "74") (name "unconnected-(MOD1-MISO2-Pad27)") (class "Default")
      (node (ref "MOD1") (pin "27") (pinfunction "MISO2_27") (pintype "bidirectional"))
    )
    (net (code "75") (name "unconnected-(MOD1-MOSI2-Pad28)") (class "Default")
      (node (ref "MOD1") (pin "28") (pinfunction "MOSI2_28") (pintype "bidirectional"))
    )
    (net (code "76") (name "unconnected-(MOD1-PWM0{slash}RED-LED-Pad21)") (class "Default")
      (node (ref "MOD1") (pin "21") (pinfunction "PWM0/RED-LED_21") (pintype "bidirectional"))
    )
    (net (code "77") (name "unconnected-(MOD1-PWM1{slash}BLUE-LED-Pad22)") (class "Default")
      (node (ref "MOD1") (pin "22") (pinfunction "PWM1/BLUE-LED_22") (pintype "bidirectional"))
    )
    (net (code "78") (name "unconnected-(MOD1-PWM2{slash}GREEN-LED-Pad23)") (class "Default")
      (node (ref "MOD1") (pin "23") (pinfunction "PWM2/GREEN-LED_23") (pintype "bidirectional"))
    )
    (net (code "79") (name "unconnected-(MOD1-SCK2-Pad26)") (class "Default")
      (node (ref "MOD1") (pin "26") (pinfunction "SCK2_26") (pintype "bidirectional"))
    )
    (net (code "80") (name "unconnected-(MOD1-SCL2-Pad29)") (class "Default")
      (node (ref "MOD1") (pin "29") (pinfunction "SCL2_29") (pintype "bidirectional"))
    )
    (net (code "81") (name "unconnected-(MOD1-SDA2-Pad30)") (class "Default")
      (node (ref "MOD1") (pin "30") (pinfunction "SDA2_30") (pintype "bidirectional"))
    )
    (net (code "82") (name "unconnected-(MOD1-TGT_CTS-Pad39)") (class "Default")
      (node (ref "MOD1") (pin "39") (pinfunction "TGT_CTS_39") (pintype "bidirectional"))
    )
    (net (code "83") (name "unconnected-(MOD1-TGT_RTS-Pad38)") (class "Default")
      (node (ref "MOD1") (pin "38") (pinfunction "TGT_RTS_38") (pintype "bidirectional"))
    )
  )
)
